# main_stack_dual_channel.net
KiCad netlist of a schematic drawn in Altium Designer
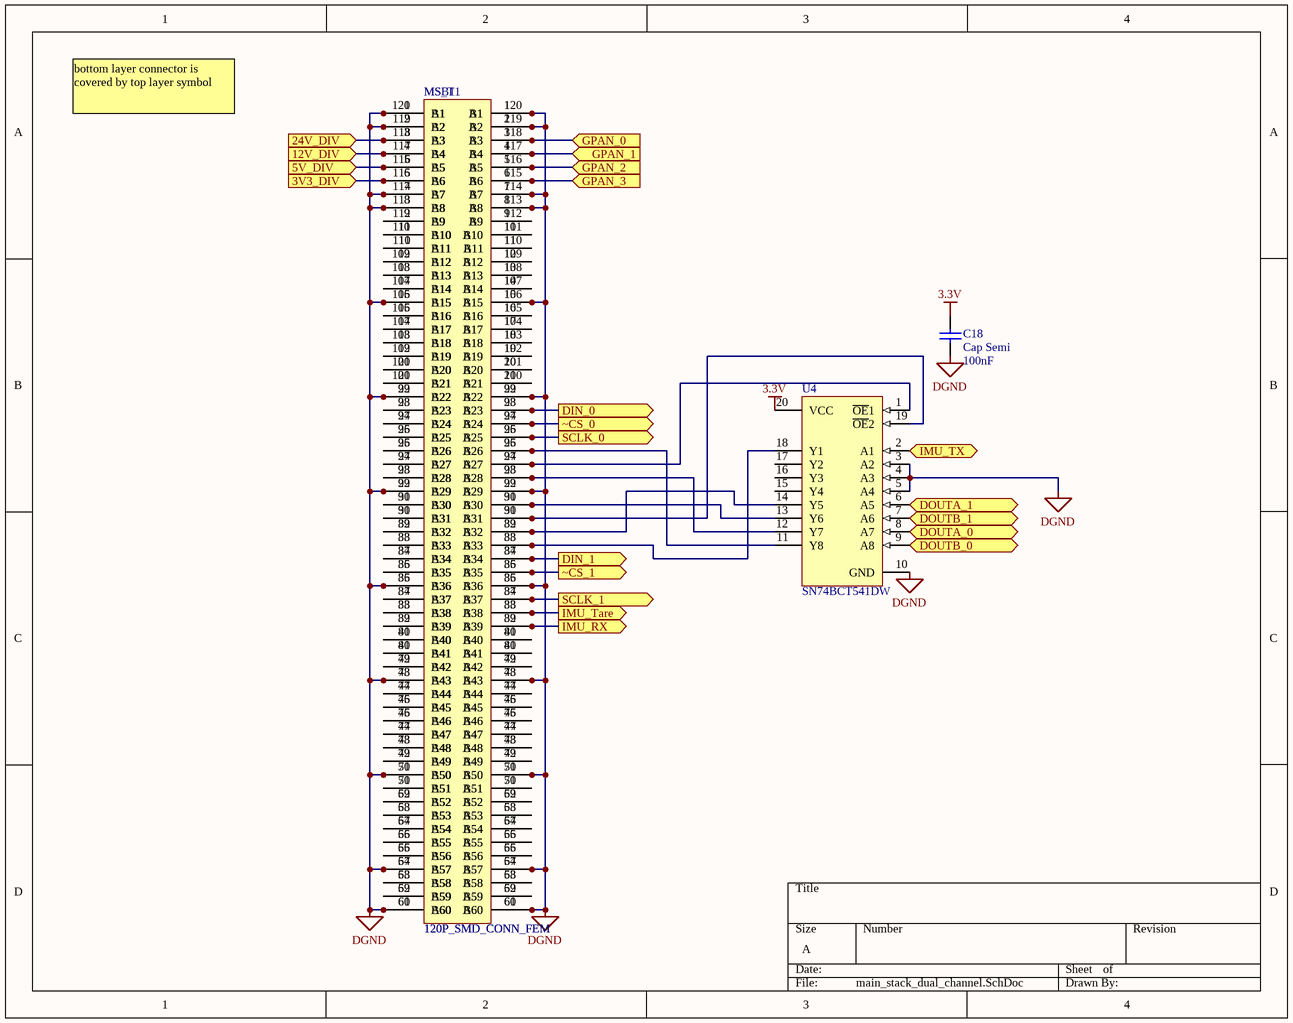
[diagram p0: main_stack_dual_channel.SchDoc]

(export (version "E")
  (design (tool "Eeschema 10.0.6"))
  (components
    (comp (ref "C18")
      (value "Cap Semi")
      (footprint "C0805")
      (description "Capacitor (Semiconductor SIM Model)")
      (fields (field (name "ALTIUM_VALUE") "100nF") (field (name "PUBLISHER") "Altium Limited"))
      (libsource (lib "Miscellaneous Devices") (part "Cap Semi"))
    )
    (comp (ref "MSB1")
      (value "120P_SMD_CONN_FEM")
      (footprint "FX2-120P-1.27SV")
      (description "Main Stack Connector, Female")
      (fields (field (name "PART NUMBER") "FX2-120P-1.27SV(71)"))
      (libsource (lib "MDA_altium_common") (part "120P_SMD_CONN_FEM"))
    )
    (comp (ref "MS_T1")
      (value "120P_SMD_CONN_FEM")
      (footprint "FX2-120P-1.27SV")
      (description "Main Stack Connector, Female")
      (fields (field (name "PART NUMBER") "FX2-120P-1.27SV(71)"))
      (libsource (lib "") (part "120P_SMD_CONN_FEM_1"))
    )
    (comp (ref "U4")
      (value "SN74BCT541DW")
      (footprint "TI Logic Buffer Line Driver:DW020")
      (description "Octal Buffer/Driver with 3-State Outputs")
      (fields (field (name "PUBLISHER") "Altium Limited"))
      (libsource (lib "TI Logic Buffer Line Driver") (part "SN74BCT541DW"))
    )
  )
  (nets
    (net (code "1") (name "/3V3_DIV") (class "Default")
      (node (ref "MSB1") (pin "115") (pinfunction "B6_115") (pintype "passive"))
      (node (ref "MS_T1") (pin "6") (pinfunction "A6_6") (pintype "passive"))
    )
    (net (code "2") (name "/5V_DIV") (class "Default")
      (node (ref "MSB1") (pin "116") (pinfunction "B5_116") (pintype "passive"))
      (node (ref "MS_T1") (pin "5") (pinfunction "A5_5") (pintype "passive"))
    )
    (net (code "3") (name "/12V_DIV") (class "Default")
      (node (ref "MSB1") (pin "117") (pinfunction "B4_117") (pintype "passive"))
      (node (ref "MS_T1") (pin "4") (pinfunction "A4_4") (pintype "passive"))
    )
    (net (code "4") (name "/24V_DIV") (class "Default")
      (node (ref "MSB1") (pin "118") (pinfunction "B3_118") (pintype "passive"))
      (node (ref "MS_T1") (pin "3") (pinfunction "A3_3") (pintype "passive"))
    )
    (net (code "5") (name "/DIN_0") (class "Default")
      (node (ref "MSB1") (pin "23") (pinfunction "A23_23") (pintype "passive"))
      (node (ref "MS_T1") (pin "98") (pinfunction "B23_98") (pintype "passive"))
    )
    (net (code "6") (name "/DIN_1") (class "Default")
      (node (ref "MSB1") (pin "34") (pinfunction "A34_34") (pintype "passive"))
      (node (ref "MS_T1") (pin "87") (pinfunction "B34_87") (pintype "passive"))
    )
    (net (code "7") (name "/DOUTA_0") (class "Default")
      (node (ref "U4") (pin "8") (pinfunction "A7_8") (pintype "input"))
    )
    (net (code "8") (name "/DOUTA_1") (class "Default")
      (node (ref "U4") (pin "6") (pinfunction "A5_6") (pintype "input"))
    )
    (net (code "9") (name "/DOUTB_0") (class "Default")
      (node (ref "U4") (pin "9") (pinfunction "A8_9") (pintype "input"))
    )
    (net (code "10") (name "/DOUTB_1") (class "Default")
      (node (ref "U4") (pin "7") (pinfunction "A6_7") (pintype "input"))
    )
    (net (code "11") (name "/GPAN_0") (class "Default")
      (node (ref "MSB1") (pin "3") (pinfunction "A3_3") (pintype "passive"))
      (node (ref "MS_T1") (pin "118") (pinfunction "B3_118") (pintype "passive"))
    )
    (net (code "12") (name "/GPAN_1") (class "Default")
      (node (ref "MSB1") (pin "4") (pinfunction "A4_4") (pintype "passive"))
      (node (ref "MS_T1") (pin "117") (pinfunction "B4_117") (pintype "passive"))
    )
    (net (code "13") (name "/GPAN_2") (class "Default")
      (node (ref "MSB1") (pin "5") (pinfunction "A5_5") (pintype "passive"))
      (node (ref "MS_T1") (pin "116") (pinfunction "B5_116") (pintype "passive"))
    )
    (net (code "14") (name "/GPAN_3") (class "Default")
      (node (ref "MSB1") (pin "6") (pinfunction "A6_6") (pintype "passive"))
      (node (ref "MS_T1") (pin "115") (pinfunction "B6_115") (pintype "passive"))
    )
    (net (code "15") (name "/IMU_RX") (class "Default")
      (node (ref "MSB1") (pin "39") (pinfunction "A39_39") (pintype "passive"))
      (node (ref "MS_T1") (pin "82") (pinfunction "B39_82") (pintype "passive"))
    )
    (net (code "16") (name "/IMU_TX") (class "Default")
      (node (ref "U4") (pin "2") (pinfunction "A1_2") (pintype "input"))
    )
    (net (code "17") (name "/IMU_Tare") (class "Default")
      (node (ref "MSB1") (pin "38") (pinfunction "A38_38") (pintype "passive"))
      (node (ref "MS_T1") (pin "83") (pinfunction "B38_83") (pintype "passive"))
    )
    (net (code "18") (name "/SCLK_0") (class "Default")
      (node (ref "MSB1") (pin "25") (pinfunction "A25_25") (pintype "passive"))
      (node (ref "MS_T1") (pin "96") (pinfunction "B25_96") (pintype "passive"))
    )
    (net (code "19") (name "/SCLK_1") (class "Default")
      (node (ref "MSB1") (pin "37") (pinfunction "A37_37") (pintype "passive"))
      (node (ref "MS_T1") (pin "84") (pinfunction "B37_84") (pintype "passive"))
    )
    (net (code "20") (name "/~CS_0") (class "Default")
      (node (ref "MSB1") (pin "24") (pinfunction "A24_24") (pintype "passive"))
      (node (ref "MS_T1") (pin "97") (pinfunction "B24_97") (pintype "passive"))
    )
    (net (code "21") (name "/~CS_1") (class "Default")
      (node (ref "MSB1") (pin "35") (pinfunction "A35_35") (pintype "passive"))
      (node (ref "MS_T1") (pin "86") (pinfunction "B35_86") (pintype "passive"))
    )
    (net (code "22") (name "3.3V") (class "Default")
      (node (ref "C18") (pin "2") (pinfunction "2_2") (pintype "passive"))
      (node (ref "U4") (pin "20") (pinfunction "VCC_20") (pintype "power_in"))
    )
    (net (code "23") (name "DGND") (class "Default")
      (node (ref "C18") (pin "1") (pinfunction "1_1") (pintype "passive"))
      (node (ref "MSB1") (pin "1") (pinfunction "A1_1") (pintype "passive"))
      (node (ref "MSB1") (pin "106") (pinfunction "B15_106") (pintype "passive"))
      (node (ref "MSB1") (pin "113") (pinfunction "B8_113") (pintype "passive"))
      (node (ref "MSB1") (pin "114") (pinfunction "B7_114") (pintype "passive"))
      (node (ref "MSB1") (pin "119") (pinfunction "B2_119") (pintype "passive"))
      (node (ref "MSB1") (pin "120") (pinfunction "B1_120") (pintype "passive"))
      (node (ref "MSB1") (pin "15") (pinfunction "A15_15") (pintype "passive"))
      (node (ref "MSB1") (pin "2") (pinfunction "A2_2") (pintype "passive"))
      (node (ref "MSB1") (pin "22") (pinfunction "A22_22") (pintype "passive"))
      (node (ref "MSB1") (pin "29") (pinfunction "A29_29") (pintype "passive"))
      (node (ref "MSB1") (pin "36") (pinfunction "A36_36") (pintype "passive"))
      (node (ref "MSB1") (pin "43") (pinfunction "A43_43") (pintype "passive"))
      (node (ref "MSB1") (pin "50") (pinfunction "A50_50") (pintype "passive"))
      (node (ref "MSB1") (pin "57") (pinfunction "A57_57") (pintype "passive"))
      (node (ref "MSB1") (pin "60") (pinfunction "A60_60") (pintype "passive"))
      (node (ref "MSB1") (pin "61") (pinfunction "B60_61") (pintype "passive"))
      (node (ref "MSB1") (pin "64") (pinfunction "B57_64") (pintype "passive"))
      (node (ref "MSB1") (pin "7") (pinfunction "A7_7") (pintype "passive"))
      (node (ref "MSB1") (pin "71") (pinfunction "B50_71") (pintype "passive"))
      (node (ref "MSB1") (pin "78") (pinfunction "B43_78") (pintype "passive"))
      (node (ref "MSB1") (pin "8") (pinfunction "A8_8") (pintype "passive"))
      (node (ref "MSB1") (pin "85") (pinfunction "B36_85") (pintype "passive"))
      (node (ref "MSB1") (pin "92") (pinfunction "B29_92") (pintype "passive"))
      (node (ref "MSB1") (pin "99") (pinfunction "B22_99") (pintype "passive"))
      (node (ref "MS_T1") (pin "1") (pinfunction "A1_1") (pintype "passive"))
      (node (ref "MS_T1") (pin "106") (pinfunction "B15_106") (pintype "passive"))
      (node (ref "MS_T1") (pin "113") (pinfunction "B8_113") (pintype "passive"))
      (node (ref "MS_T1") (pin "114") (pinfunction "B7_114") (pintype "passive"))
      (node (ref "MS_T1") (pin "119") (pinfunction "B2_119") (pintype "passive"))
      (node (ref "MS_T1") (pin "120") (pinfunction "B1_120") (pintype "passive"))
      (node (ref "MS_T1") (pin "15") (pinfunction "A15_15") (pintype "passive"))
      (node (ref "MS_T1") (pin "2") (pinfunction "A2_2") (pintype "passive"))
      (node (ref "MS_T1") (pin "22") (pinfunction "A22_22") (pintype "passive"))
      (node (ref "MS_T1") (pin "29") (pinfunction "A29_29") (pintype "passive"))
      (node (ref "MS_T1") (pin "36") (pinfunction "A36_36") (pintype "passive"))
      (node (ref "MS_T1") (pin "43") (pinfunction "A43_43") (pintype "passive"))
      (node (ref "MS_T1") (pin "50") (pinfunction "A50_50") (pintype "passive"))
      (node (ref "MS_T1") (pin "57") (pinfunction "A57_57") (pintype "passive"))
      (node (ref "MS_T1") (pin "60") (pinfunction "A60_60") (pintype "passive"))
      (node (ref "MS_T1") (pin "61") (pinfunction "B60_61") (pintype "passive"))
      (node (ref "MS_T1") (pin "64") (pinfunction "B57_64") (pintype "passive"))
      (node (ref "MS_T1") (pin "7") (pinfunction "A7_7") (pintype "passive"))
      (node (ref "MS_T1") (pin "71") (pinfunction "B50_71") (pintype "passive"))
      (node (ref "MS_T1") (pin "78") (pinfunction "B43_78") (pintype "passive"))
      (node (ref "MS_T1") (pin "8") (pinfunction "A8_8") (pintype "passive"))
      (node (ref "MS_T1") (pin "85") (pinfunction "B36_85") (pintype "passive"))
      (node (ref "MS_T1") (pin "92") (pinfunction "B29_92") (pintype "passive"))
      (node (ref "MS_T1") (pin "99") (pinfunction "B22_99") (pintype "passive"))
      (node (ref "U4") (pin "10") (pinfunction "GND_10") (pintype "power_in"))
      (node (ref "U4") (pin "3") (pinfunction "A2_3") (pintype "input"))
      (node (ref "U4") (pin "4") (pinfunction "A3_4") (pintype "input"))
      (node (ref "U4") (pin "5") (pinfunction "A4_5") (pintype "input"))
    )
    (net (code "24") (name "Net-(MSB1-A9)") (class "Default")
      (node (ref "MSB1") (pin "9") (pinfunction "A9_9") (pintype "passive"))
      (node (ref "MS_T1") (pin "112") (pinfunction "B9_112") (pintype "passive"))
    )
    (net (code "25") (name "Net-(MSB1-A10)") (class "Default")
      (node (ref "MSB1") (pin "10") (pinfunction "A10_10") (pintype "passive"))
      (node (ref "MS_T1") (pin "111") (pinfunction "B10_111") (pintype "passive"))
    )
    (net (code "26") (name "Net-(MSB1-A11)") (class "Default")
      (node (ref "MSB1") (pin "11") (pinfunction "A11_11") (pintype "passive"))
      (node (ref "MS_T1") (pin "110") (pinfunction "B11_110") (pintype "passive"))
    )
    (net (code "27") (name "Net-(MSB1-A12)") (class "Default")
      (node (ref "MSB1") (pin "12") (pinfunction "A12_12") (pintype "passive"))
      (node (ref "MS_T1") (pin "109") (pinfunction "B12_109") (pintype "passive"))
    )
    (net (code "28") (name "Net-(MSB1-A13)") (class "Default")
      (node (ref "MSB1") (pin "13") (pinfunction "A13_13") (pintype "passive"))
      (node (ref "MS_T1") (pin "108") (pinfunction "B13_108") (pintype "passive"))
    )
    (net (code "29") (name "Net-(MSB1-A14)") (class "Default")
      (node (ref "MSB1") (pin "14") (pinfunction "A14_14") (pintype "passive"))
      (node (ref "MS_T1") (pin "107") (pinfunction "B14_107") (pintype "passive"))
    )
    (net (code "30") (name "Net-(MSB1-A16)") (class "Default")
      (node (ref "MSB1") (pin "16") (pinfunction "A16_16") (pintype "passive"))
      (node (ref "MS_T1") (pin "105") (pinfunction "B16_105") (pintype "passive"))
    )
    (net (code "31") (name "Net-(MSB1-A17)") (class "Default")
      (node (ref "MSB1") (pin "17") (pinfunction "A17_17") (pintype "passive"))
      (node (ref "MS_T1") (pin "104") (pinfunction "B17_104") (pintype "passive"))
    )
    (net (code "32") (name "Net-(MSB1-A18)") (class "Default")
      (node (ref "MSB1") (pin "18") (pinfunction "A18_18") (pintype "passive"))
      (node (ref "MS_T1") (pin "103") (pinfunction "B18_103") (pintype "passive"))
    )
    (net (code "33") (name "Net-(MSB1-A19)") (class "Default")
      (node (ref "MSB1") (pin "19") (pinfunction "A19_19") (pintype "passive"))
      (node (ref "MS_T1") (pin "102") (pinfunction "B19_102") (pintype "passive"))
    )
    (net (code "34") (name "Net-(MSB1-A20)") (class "Default")
      (node (ref "MSB1") (pin "20") (pinfunction "A20_20") (pintype "passive"))
      (node (ref "MS_T1") (pin "101") (pinfunction "B20_101") (pintype "passive"))
    )
    (net (code "35") (name "Net-(MSB1-A21)") (class "Default")
      (node (ref "MSB1") (pin "21") (pinfunction "A21_21") (pintype "passive"))
      (node (ref "MS_T1") (pin "100") (pinfunction "B21_100") (pintype "passive"))
    )
    (net (code "36") (name "Net-(MSB1-A26)") (class "Default")
      (node (ref "MSB1") (pin "26") (pinfunction "A26_26") (pintype "passive"))
      (node (ref "MS_T1") (pin "95") (pinfunction "B26_95") (pintype "passive"))
      (node (ref "U4") (pin "11") (pinfunction "Y8_11") (pintype "tri_state"))
    )
    (net (code "37") (name "Net-(MSB1-A27)") (class "Default")
      (node (ref "MSB1") (pin "27") (pinfunction "A27_27") (pintype "passive"))
      (node (ref "MS_T1") (pin "94") (pinfunction "B27_94") (pintype "passive"))
      (node (ref "U4") (pin "1") (pinfunction "~{OE}1_1") (pintype "input"))
    )
    (net (code "38") (name "Net-(MSB1-A28)") (class "Default")
      (node (ref "MSB1") (pin "28") (pinfunction "A28_28") (pintype "passive"))
      (node (ref "MS_T1") (pin "93") (pinfunction "B28_93") (pintype "passive"))
      (node (ref "U4") (pin "12") (pinfunction "Y7_12") (pintype "tri_state"))
    )
    (net (code "39") (name "Net-(MSB1-A30)") (class "Default")
      (node (ref "MSB1") (pin "30") (pinfunction "A30_30") (pintype "passive"))
      (node (ref "MS_T1") (pin "91") (pinfunction "B30_91") (pintype "passive"))
      (node (ref "U4") (pin "13") (pinfunction "Y6_13") (pintype "tri_state"))
    )
    (net (code "40") (name "Net-(MSB1-A31)") (class "Default")
      (node (ref "MSB1") (pin "31") (pinfunction "A31_31") (pintype "passive"))
      (node (ref "MS_T1") (pin "90") (pinfunction "B31_90") (pintype "passive"))
      (node (ref "U4") (pin "19") (pinfunction "~{OE}2_19") (pintype "input"))
    )
    (net (code "41") (name "Net-(MSB1-A32)") (class "Default")
      (node (ref "MSB1") (pin "32") (pinfunction "A32_32") (pintype "passive"))
      (node (ref "MS_T1") (pin "89") (pinfunction "B32_89") (pintype "passive"))
      (node (ref "U4") (pin "14") (pinfunction "Y5_14") (pintype "tri_state"))
    )
    (net (code "42") (name "Net-(MSB1-A33)") (class "Default")
      (node (ref "MSB1") (pin "33") (pinfunction "A33_33") (pintype "passive"))
      (node (ref "MS_T1") (pin "88") (pinfunction "B33_88") (pintype "passive"))
      (node (ref "U4") (pin "18") (pinfunction "Y1_18") (pintype "tri_state"))
    )
    (net (code "43") (name "Net-(MSB1-A40)") (class "Default")
      (node (ref "MSB1") (pin "40") (pinfunction "A40_40") (pintype "passive"))
      (node (ref "MS_T1") (pin "81") (pinfunction "B40_81") (pintype "passive"))
    )
    (net (code "44") (name "Net-(MSB1-A41)") (class "Default")
      (node (ref "MSB1") (pin "41") (pinfunction "A41_41") (pintype "passive"))
      (node (ref "MS_T1") (pin "80") (pinfunction "B41_80") (pintype "passive"))
    )
    (net (code "45") (name "Net-(MSB1-A42)") (class "Default")
      (node (ref "MSB1") (pin "42") (pinfunction "A42_42") (pintype "passive"))
      (node (ref "MS_T1") (pin "79") (pinfunction "B42_79") (pintype "passive"))
    )
    (net (code "46") (name "Net-(MSB1-A44)") (class "Default")
      (node (ref "MSB1") (pin "44") (pinfunction "A44_44") (pintype "passive"))
      (node (ref "MS_T1") (pin "77") (pinfunction "B44_77") (pintype "passive"))
    )
    (net (code "47") (name "Net-(MSB1-A45)") (class "Default")
      (node (ref "MSB1") (pin "45") (pinfunction "A45_45") (pintype "passive"))
      (node (ref "MS_T1") (pin "76") (pinfunction "B45_76") (pintype "passive"))
    )
    (net (code "48") (name "Net-(MSB1-A46)") (class "Default")
      (node (ref "MSB1") (pin "46") (pinfunction "A46_46") (pintype "passive"))
      (node (ref "MS_T1") (pin "75") (pinfunction "B46_75") (pintype "passive"))
    )
    (net (code "49") (name "Net-(MSB1-A47)") (class "Default")
      (node (ref "MSB1") (pin "47") (pinfunction "A47_47") (pintype "passive"))
      (node (ref "MS_T1") (pin "74") (pinfunction "B47_74") (pintype "passive"))
    )
    (net (code "50") (name "Net-(MSB1-A48)") (class "Default")
      (node (ref "MSB1") (pin "48") (pinfunction "A48_48") (pintype "passive"))
      (node (ref "MS_T1") (pin "73") (pinfunction "B48_73") (pintype "passive"))
    )
    (net (code "51") (name "Net-(MSB1-A49)") (class "Default")
      (node (ref "MSB1") (pin "49") (pinfunction "A49_49") (pintype "passive"))
      (node (ref "MS_T1") (pin "72") (pinfunction "B49_72") (pintype "passive"))
    )
    (net (code "52") (name "Net-(MSB1-A51)") (class "Default")
      (node (ref "MSB1") (pin "51") (pinfunction "A51_51") (pintype "passive"))
      (node (ref "MS_T1") (pin "70") (pinfunction "B51_70") (pintype "passive"))
    )
    (net (code "53") (name "Net-(MSB1-A52)") (class "Default")
      (node (ref "MSB1") (pin "52") (pinfunction "A52_52") (pintype "passive"))
      (node (ref "MS_T1") (pin "69") (pinfunction "B52_69") (pintype "passive"))
    )
    (net (code "54") (name "Net-(MSB1-A53)") (class "Default")
      (node (ref "MSB1") (pin "53") (pinfunction "A53_53") (pintype "passive"))
      (node (ref "MS_T1") (pin "68") (pinfunction "B53_68") (pintype "passive"))
    )
    (net (code "55") (name "Net-(MSB1-A54)") (class "Default")
      (node (ref "MSB1") (pin "54") (pinfunction "A54_54") (pintype "passive"))
      (node (ref "MS_T1") (pin "67") (pinfunction "B54_67") (pintype "passive"))
    )
    (net (code "56") (name "Net-(MSB1-A55)") (class "Default")
      (node (ref "MSB1") (pin "55") (pinfunction "A55_55") (pintype "passive"))
      (node (ref "MS_T1") (pin "66") (pinfunction "B55_66") (pintype "passive"))
    )
    (net (code "57") (name "Net-(MSB1-A56)") (class "Default")
      (node (ref "MSB1") (pin "56") (pinfunction "A56_56") (pintype "passive"))
      (node (ref "MS_T1") (pin "65") (pinfunction "B56_65") (pintype "passive"))
    )
    (net (code "58") (name "Net-(MSB1-A58)") (class "Default")
      (node (ref "MSB1") (pin "58") (pinfunction "A58_58") (pintype "passive"))
      (node (ref "MS_T1") (pin "63") (pinfunction "B58_63") (pintype "passive"))
    )
    (net (code "59") (name "Net-(MSB1-A59)") (class "Default")
      (node (ref "MSB1") (pin "59") (pinfunction "A59_59") (pintype "passive"))
      (node (ref "MS_T1") (pin "62") (pinfunction "B59_62") (pintype "passive"))
    )
    (net (code "60") (name "Net-(MSB1-B9)") (class "Default")
      (node (ref "MSB1") (pin "112") (pinfunction "B9_112") (pintype "passive"))
      (node (ref "MS_T1") (pin "9") (pinfunction "A9_9") (pintype "passive"))
    )
    (net (code "61") (name "Net-(MSB1-B10)") (class "Default")
      (node (ref "MSB1") (pin "111") (pinfunction "B10_111") (pintype "passive"))
      (node (ref "MS_T1") (pin "10") (pinfunction "A10_10") (pintype "passive"))
    )
    (net (code "62") (name "Net-(MSB1-B11)") (class "Default")
      (node (ref "MSB1") (pin "110") (pinfunction "B11_110") (pintype "passive"))
      (node (ref "MS_T1") (pin "11") (pinfunction "A11_11") (pintype "passive"))
    )
    (net (code "63") (name "Net-(MSB1-B12)") (class "Default")
      (node (ref "MSB1") (pin "109") (pinfunction "B12_109") (pintype "passive"))
      (node (ref "MS_T1") (pin "12") (pinfunction "A12_12") (pintype "passive"))
    )
    (net (code "64") (name "Net-(MSB1-B13)") (class "Default")
      (node (ref "MSB1") (pin "108") (pinfunction "B13_108") (pintype "passive"))
      (node (ref "MS_T1") (pin "13") (pinfunction "A13_13") (pintype "passive"))
    )
    (net (code "65") (name "Net-(MSB1-B14)") (class "Default")
      (node (ref "MSB1") (pin "107") (pinfunction "B14_107") (pintype "passive"))
      (node (ref "MS_T1") (pin "14") (pinfunction "A14_14") (pintype "passive"))
    )
    (net (code "66") (name "Net-(MSB1-B16)") (class "Default")
      (node (ref "MSB1") (pin "105") (pinfunction "B16_105") (pintype "passive"))
      (node (ref "MS_T1") (pin "16") (pinfunction "A16_16") (pintype "passive"))
    )
    (net (code "67") (name "Net-(MSB1-B17)") (class "Default")
      (node (ref "MSB1") (pin "104") (pinfunction "B17_104") (pintype "passive"))
      (node (ref "MS_T1") (pin "17") (pinfunction "A17_17") (pintype "passive"))
    )
    (net (code "68") (name "Net-(MSB1-B18)") (class "Default")
      (node (ref "MSB1") (pin "103") (pinfunction "B18_103") (pintype "passive"))
      (node (ref "MS_T1") (pin "18") (pinfunction "A18_18") (pintype "passive"))
    )
    (net (code "69") (name "Net-(MSB1-B19)") (class "Default")
      (node (ref "MSB1") (pin "102") (pinfunction "B19_102") (pintype "passive"))
      (node (ref "MS_T1") (pin "19") (pinfunction "A19_19") (pintype "passive"))
    )
    (net (code "70") (name "Net-(MSB1-B20)") (class "Default")
      (node (ref "MSB1") (pin "101") (pinfunction "B20_101") (pintype "passive"))
      (node (ref "MS_T1") (pin "20") (pinfunction "A20_20") (pintype "passive"))
    )
    (net (code "71") (name "Net-(MSB1-B21)") (class "Default")
      (node (ref "MSB1") (pin "100") (pinfunction "B21_100") (pintype "passive"))
      (node (ref "MS_T1") (pin "21") (pinfunction "A21_21") (pintype "passive"))
    )
    (net (code "72") (name "Net-(MSB1-B23)") (class "Default")
      (node (ref "MSB1") (pin "98") (pinfunction "B23_98") (pintype "passive"))
      (node (ref "MS_T1") (pin "23") (pinfunction "A23_23") (pintype "passive"))
    )
    (net (code "73") (name "Net-(MSB1-B24)") (class "Default")
      (node (ref "MSB1") (pin "97") (pinfunction "B24_97") (pintype "passive"))
      (node (ref "MS_T1") (pin "24") (pinfunction "A24_24") (pintype "passive"))
    )
    (net (code "74") (name "Net-(MSB1-B25)") (class "Default")
      (node (ref "MSB1") (pin "96") (pinfunction "B25_96") (pintype "passive"))
      (node (ref "MS_T1") (pin "25") (pinfunction "A25_25") (pintype "passive"))
    )
    (net (code "75") (name "Net-(MSB1-B26)") (class "Default")
      (node (ref "MSB1") (pin "95") (pinfunction "B26_95") (pintype "passive"))
      (node (ref "MS_T1") (pin "26") (pinfunction "A26_26") (pintype "passive"))
    )
    (net (code "76") (name "Net-(MSB1-B27)") (class "Default")
      (node (ref "MSB1") (pin "94") (pinfunction "B27_94") (pintype "passive"))
      (node (ref "MS_T1") (pin "27") (pinfunction "A27_27") (pintype "passive"))
    )
    (net (code "77") (name "Net-(MSB1-B28)") (class "Default")
      (node (ref "MSB1") (pin "93") (pinfunction "B28_93") (pintype "passive"))
      (node (ref "MS_T1") (pin "28") (pinfunction "A28_28") (pintype "passive"))
    )
    (net (code "78") (name "Net-(MSB1-B30)") (class "Default")
      (node (ref "MSB1") (pin "91") (pinfunction "B30_91") (pintype "passive"))
      (node (ref "MS_T1") (pin "30") (pinfunction "A30_30") (pintype "passive"))
    )
    (net (code "79") (name "Net-(MSB1-B31)") (class "Default")
      (node (ref "MSB1") (pin "90") (pinfunction "B31_90") (pintype "passive"))
      (node (ref "MS_T1") (pin "31") (pinfunction "A31_31") (pintype "passive"))
    )
    (net (code "80") (name "Net-(MSB1-B32)") (class "Default")
      (node (ref "MSB1") (pin "89") (pinfunction "B32_89") (pintype "passive"))
      (node (ref "MS_T1") (pin "32") (pinfunction "A32_32") (pintype "passive"))
    )
    (net (code "81") (name "Net-(MSB1-B33)") (class "Default")
      (node (ref "MSB1") (pin "88") (pinfunction "B33_88") (pintype "passive"))
      (node (ref "MS_T1") (pin "33") (pinfunction "A33_33") (pintype "passive"))
    )
    (net (code "82") (name "Net-(MSB1-B34)") (class "Default")
      (node (ref "MSB1") (pin "87") (pinfunction "B34_87") (pintype "passive"))
      (node (ref "MS_T1") (pin "34") (pinfunction "A34_34") (pintype "passive"))
    )
    (net (code "83") (name "Net-(MSB1-B35)") (class "Default")
      (node (ref "MSB1") (pin "86") (pinfunction "B35_86") (pintype "passive"))
      (node (ref "MS_T1") (pin "35") (pinfunction "A35_35") (pintype "passive"))
    )
    (net (code "84") (name "Net-(MSB1-B37)") (class "Default")
      (node (ref "MSB1") (pin "84") (pinfunction "B37_84") (pintype "passive"))
      (node (ref "MS_T1") (pin "37") (pinfunction "A37_37") (pintype "passive"))
    )
    (net (code "85") (name "Net-(MSB1-B38)") (class "Default")
      (node (ref "MSB1") (pin "83") (pinfunction "B38_83") (pintype "passive"))
      (node (ref "MS_T1") (pin "38") (pinfunction "A38_38") (pintype "passive"))
    )
    (net (code "86") (name "Net-(MSB1-B39)") (class "Default")
      (node (ref "MSB1") (pin "82") (pinfunction "B39_82") (pintype "passive"))
      (node (ref "MS_T1") (pin "39") (pinfunction "A39_39") (pintype "passive"))
    )
    (net (code "87") (name "Net-(MSB1-B40)") (class "Default")
      (node (ref "MSB1") (pin "81") (pinfunction "B40_81") (pintype "passive"))
      (node (ref "MS_T1") (pin "40") (pinfunction "A40_40") (pintype "passive"))
    )
    (net (code "88") (name "Net-(MSB1-B41)") (class "Default")
      (node (ref "MSB1") (pin "80") (pinfunction "B41_80") (pintype "passive"))
      (node (ref "MS_T1") (pin "41") (pinfunction "A41_41") (pintype "passive"))
    )
    (net (code "89") (name "Net-(MSB1-B42)") (class "Default")
      (node (ref "MSB1") (pin "79") (pinfunction "B42_79") (pintype "passive"))
      (node (ref "MS_T1") (pin "42") (pinfunction "A42_42") (pintype "passive"))
    )
    (net (code "90") (name "Net-(MSB1-B44)") (class "Default")
      (node (ref "MSB1") (pin "77") (pinfunction "B44_77") (pintype "passive"))
      (node (ref "MS_T1") (pin "44") (pinfunction "A44_44") (pintype "passive"))
    )
    (net (code "91") (name "Net-(MSB1-B45)") (class "Default")
      (node (ref "MSB1") (pin "76") (pinfunction "B45_76") (pintype "passive"))
      (node (ref "MS_T1") (pin "45") (pinfunction "A45_45") (pintype "passive"))
    )
    (net (code "92") (name "Net-(MSB1-B46)") (class "Default")
      (node (ref "MSB1") (pin "75") (pinfunction "B46_75") (pintype "passive"))
      (node (ref "MS_T1") (pin "46") (pinfunction "A46_46") (pintype "passive"))
    )
    (net (code "93") (name "Net-(MSB1-B47)") (class "Default")
      (node (ref "MSB1") (pin "74") (pinfunction "B47_74") (pintype "passive"))
      (node (ref "MS_T1") (pin "47") (pinfunction "A47_47") (pintype "passive"))
    )
    (net (code "94") (name "Net-(MSB1-B48)") (class "Default")
      (node (ref "MSB1") (pin "73") (pinfunction "B48_73") (pintype "passive"))
      (node (ref "MS_T1") (pin "48") (pinfunction "A48_48") (pintype "passive"))
    )
    (net (code "95") (name "Net-(MSB1-B49)") (class "Default")
      (node (ref "MSB1") (pin "72") (pinfunction "B49_72") (pintype "passive"))
      (node (ref "MS_T1") (pin "49") (pinfunction "A49_49") (pintype "passive"))
    )
    (net (code "96") (name "Net-(MSB1-B51)") (class "Default")
      (node (ref "MSB1") (pin "70") (pinfunction "B51_70") (pintype "passive"))
      (node (ref "MS_T1") (pin "51") (pinfunction "A51_51") (pintype "passive"))
    )
    (net (code "97") (name "Net-(MSB1-B52)") (class "Default")
      (node (ref "MSB1") (pin "69") (pinfunction "B52_69") (pintype "passive"))
      (node (ref "MS_T1") (pin "52") (pinfunction "A52_52") (pintype "passive"))
    )
    (net (code "98") (name "Net-(MSB1-B53)") (class "Default")
      (node (ref "MSB1") (pin "68") (pinfunction "B53_68") (pintype "passive"))
      (node (ref "MS_T1") (pin "53") (pinfunction "A53_53") (pintype "passive"))
    )
    (net (code "99") (name "Net-(MSB1-B54)") (class "Default")
      (node (ref "MSB1") (pin "67") (pinfunction "B54_67") (pintype "passive"))
      (node (ref "MS_T1") (pin "54") (pinfunction "A54_54") (pintype "passive"))
    )
    (net (code "100") (name "Net-(MSB1-B55)") (class "Default")
      (node (ref "MSB1") (pin "66") (pinfunction "B55_66") (pintype "passive"))
      (node (ref "MS_T1") (pin "55") (pinfunction "A55_55") (pintype "passive"))
    )
    (net (code "101") (name "Net-(MSB1-B56)") (class "Default")
      (node (ref "MSB1") (pin "65") (pinfunction "B56_65") (pintype "passive"))
      (node (ref "MS_T1") (pin "56") (pinfunction "A56_56") (pintype "passive"))
    )
    (net (code "102") (name "Net-(MSB1-B58)") (class "Default")
      (node (ref "MSB1") (pin "63") (pinfunction "B58_63") (pintype "passive"))
      (node (ref "MS_T1") (pin "58") (pinfunction "A58_58") (pintype "passive"))
    )
    (net (code "103") (name "Net-(MSB1-B59)") (class "Default")
      (node (ref "MSB1") (pin "62") (pinfunction "B59_62") (pintype "passive"))
      (node (ref "MS_T1") (pin "59") (pinfunction "A59_59") (pintype "passive"))
    )
    (net (code "104") (name "unconnected-(U4-Y2-Pad17)") (class "Default")
      (node (ref "U4") (pin "17") (pinfunction "Y2_17") (pintype "tri_state"))
    )
    (net (code "105") (name "unconnected-(U4-Y3-Pad16)") (class "Default")
      (node (ref "U4") (pin "16") (pinfunction "Y3_16") (pintype "tri_state"))
    )
    (net (code "106") (name "unconnected-(U4-Y4-Pad15)") (class "Default")
      (node (ref "U4") (pin "15") (pinfunction "Y4_15") (pintype "tri_state"))
    )
  )
)
